# 0529_Agent_KitRev0103.net
KiCad netlist of a schematic drawn in EAGLE
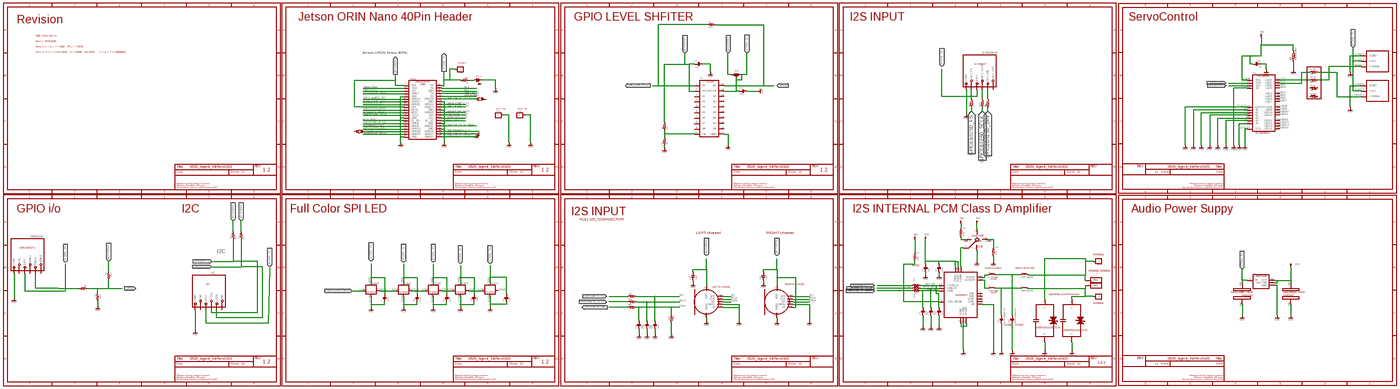
[diagram p0: schematic, sheet 1, overview]
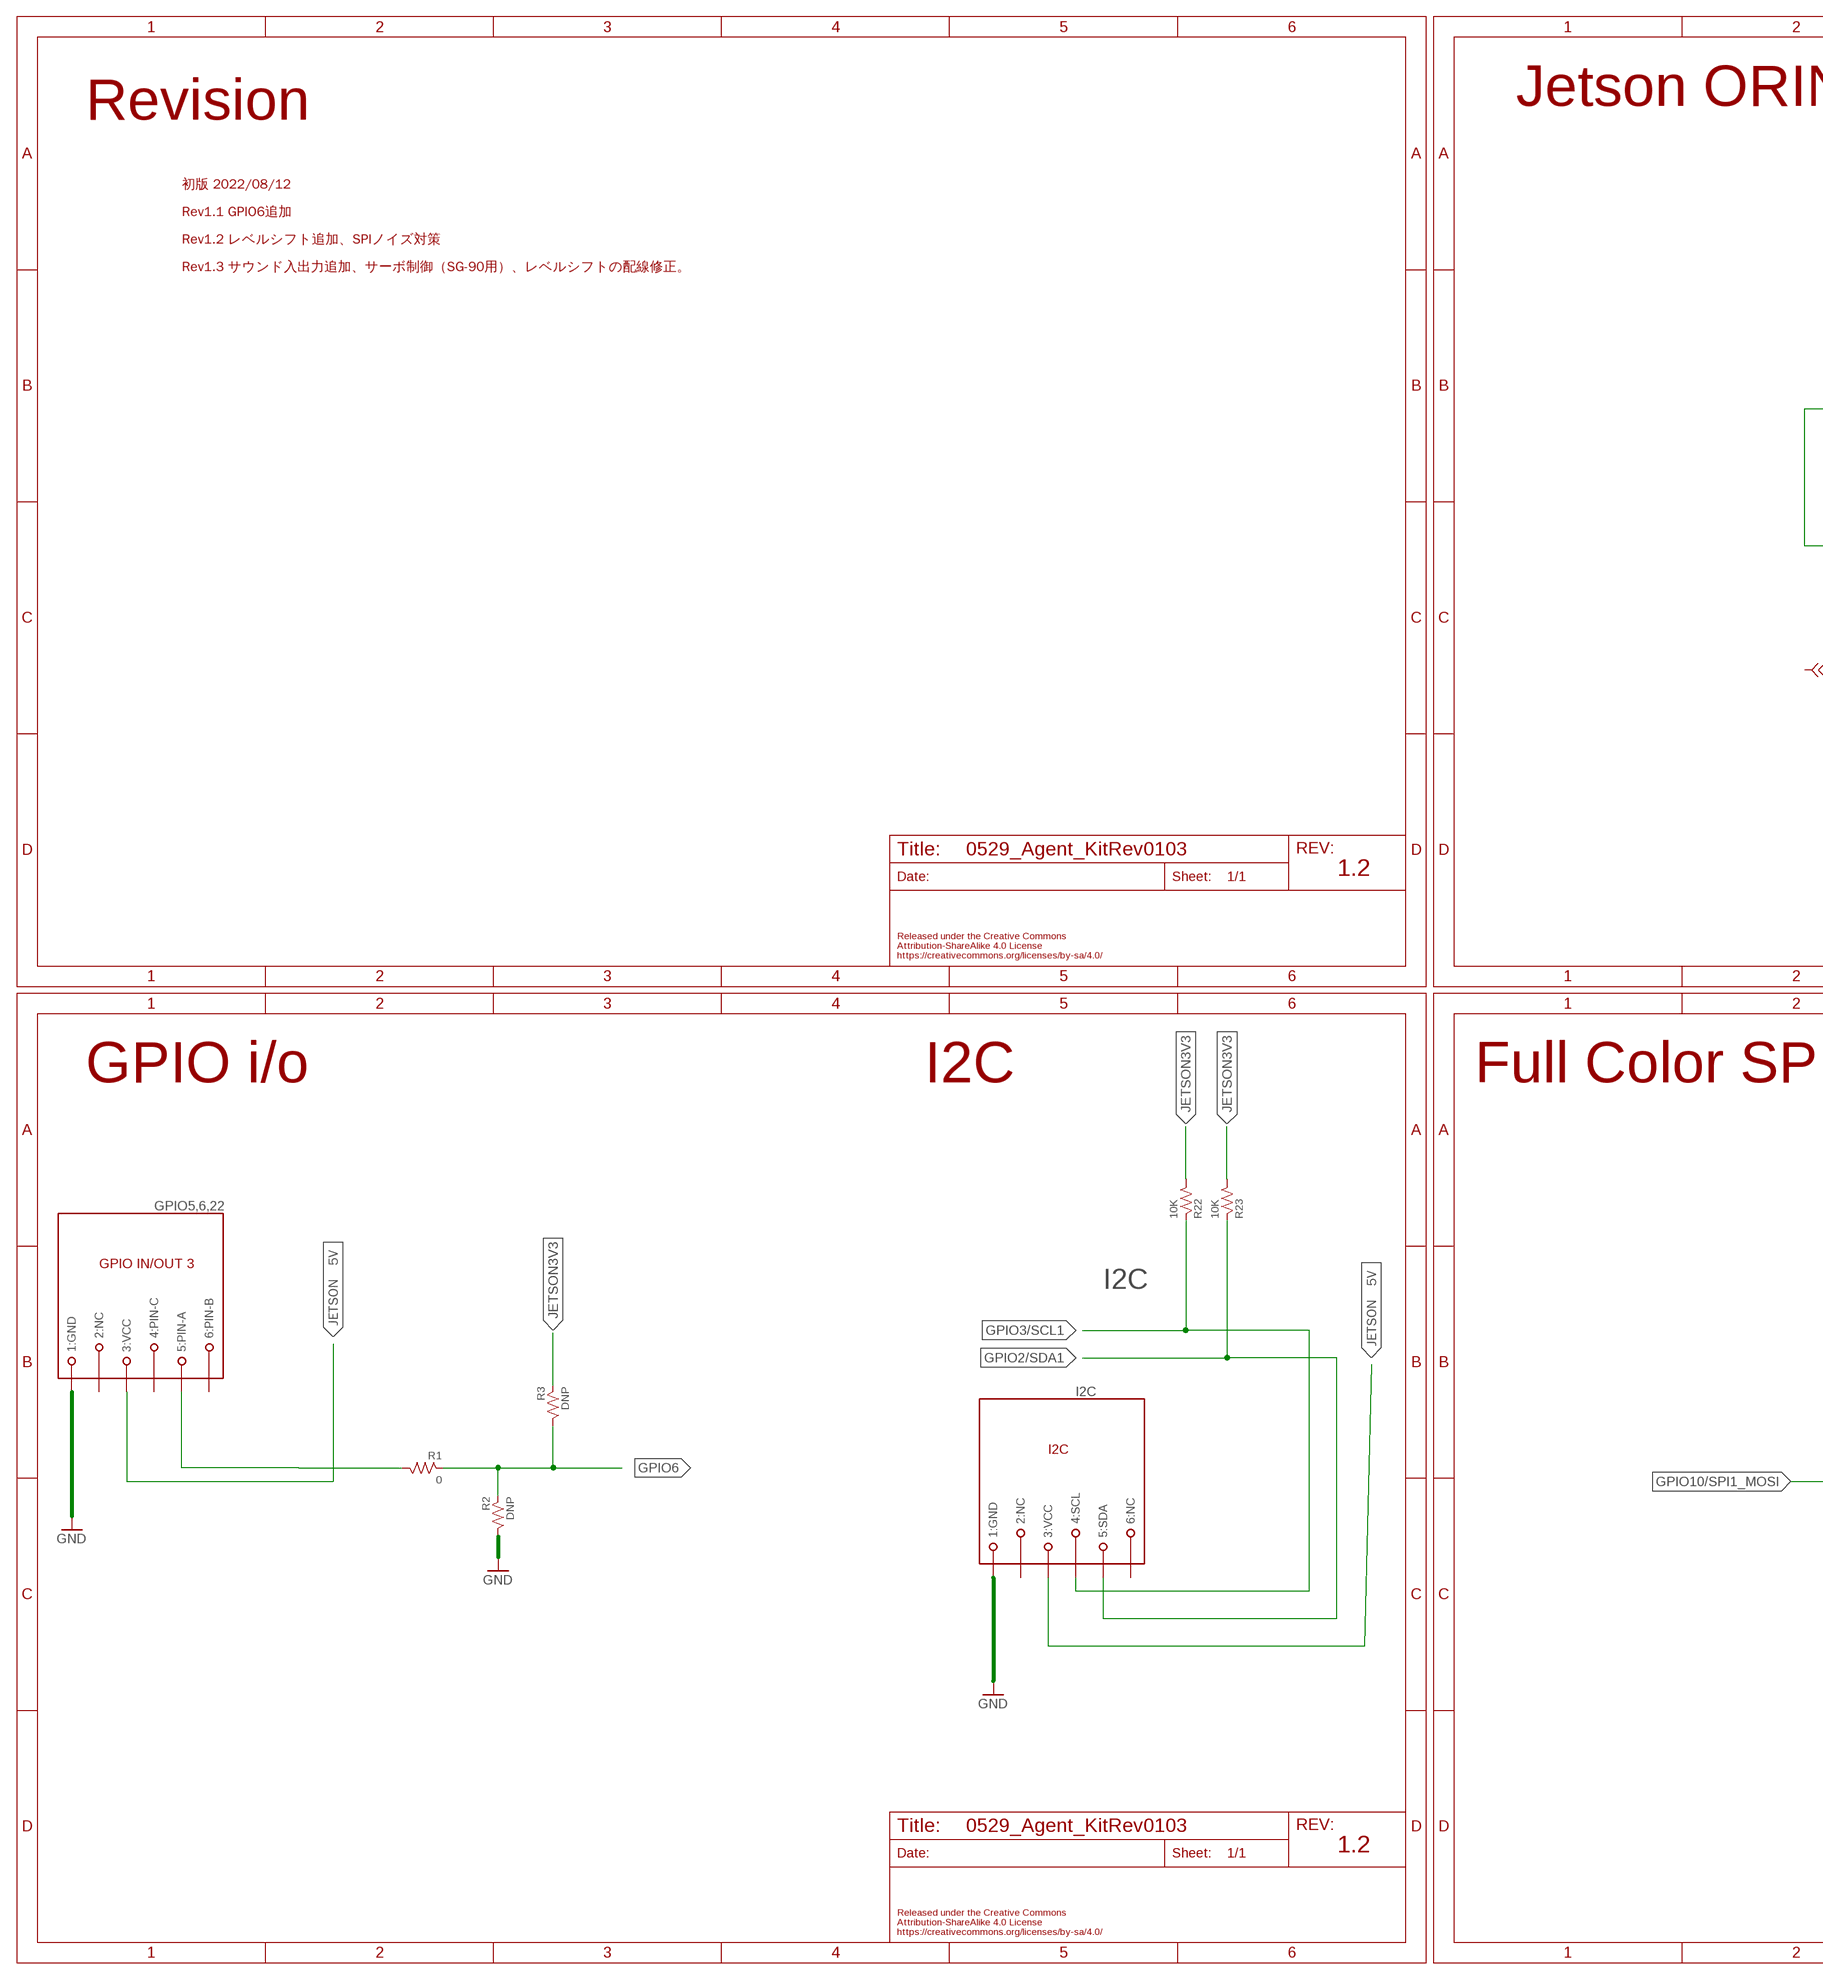
[diagram p1: schematic, sheet 1, part 1 of 4]
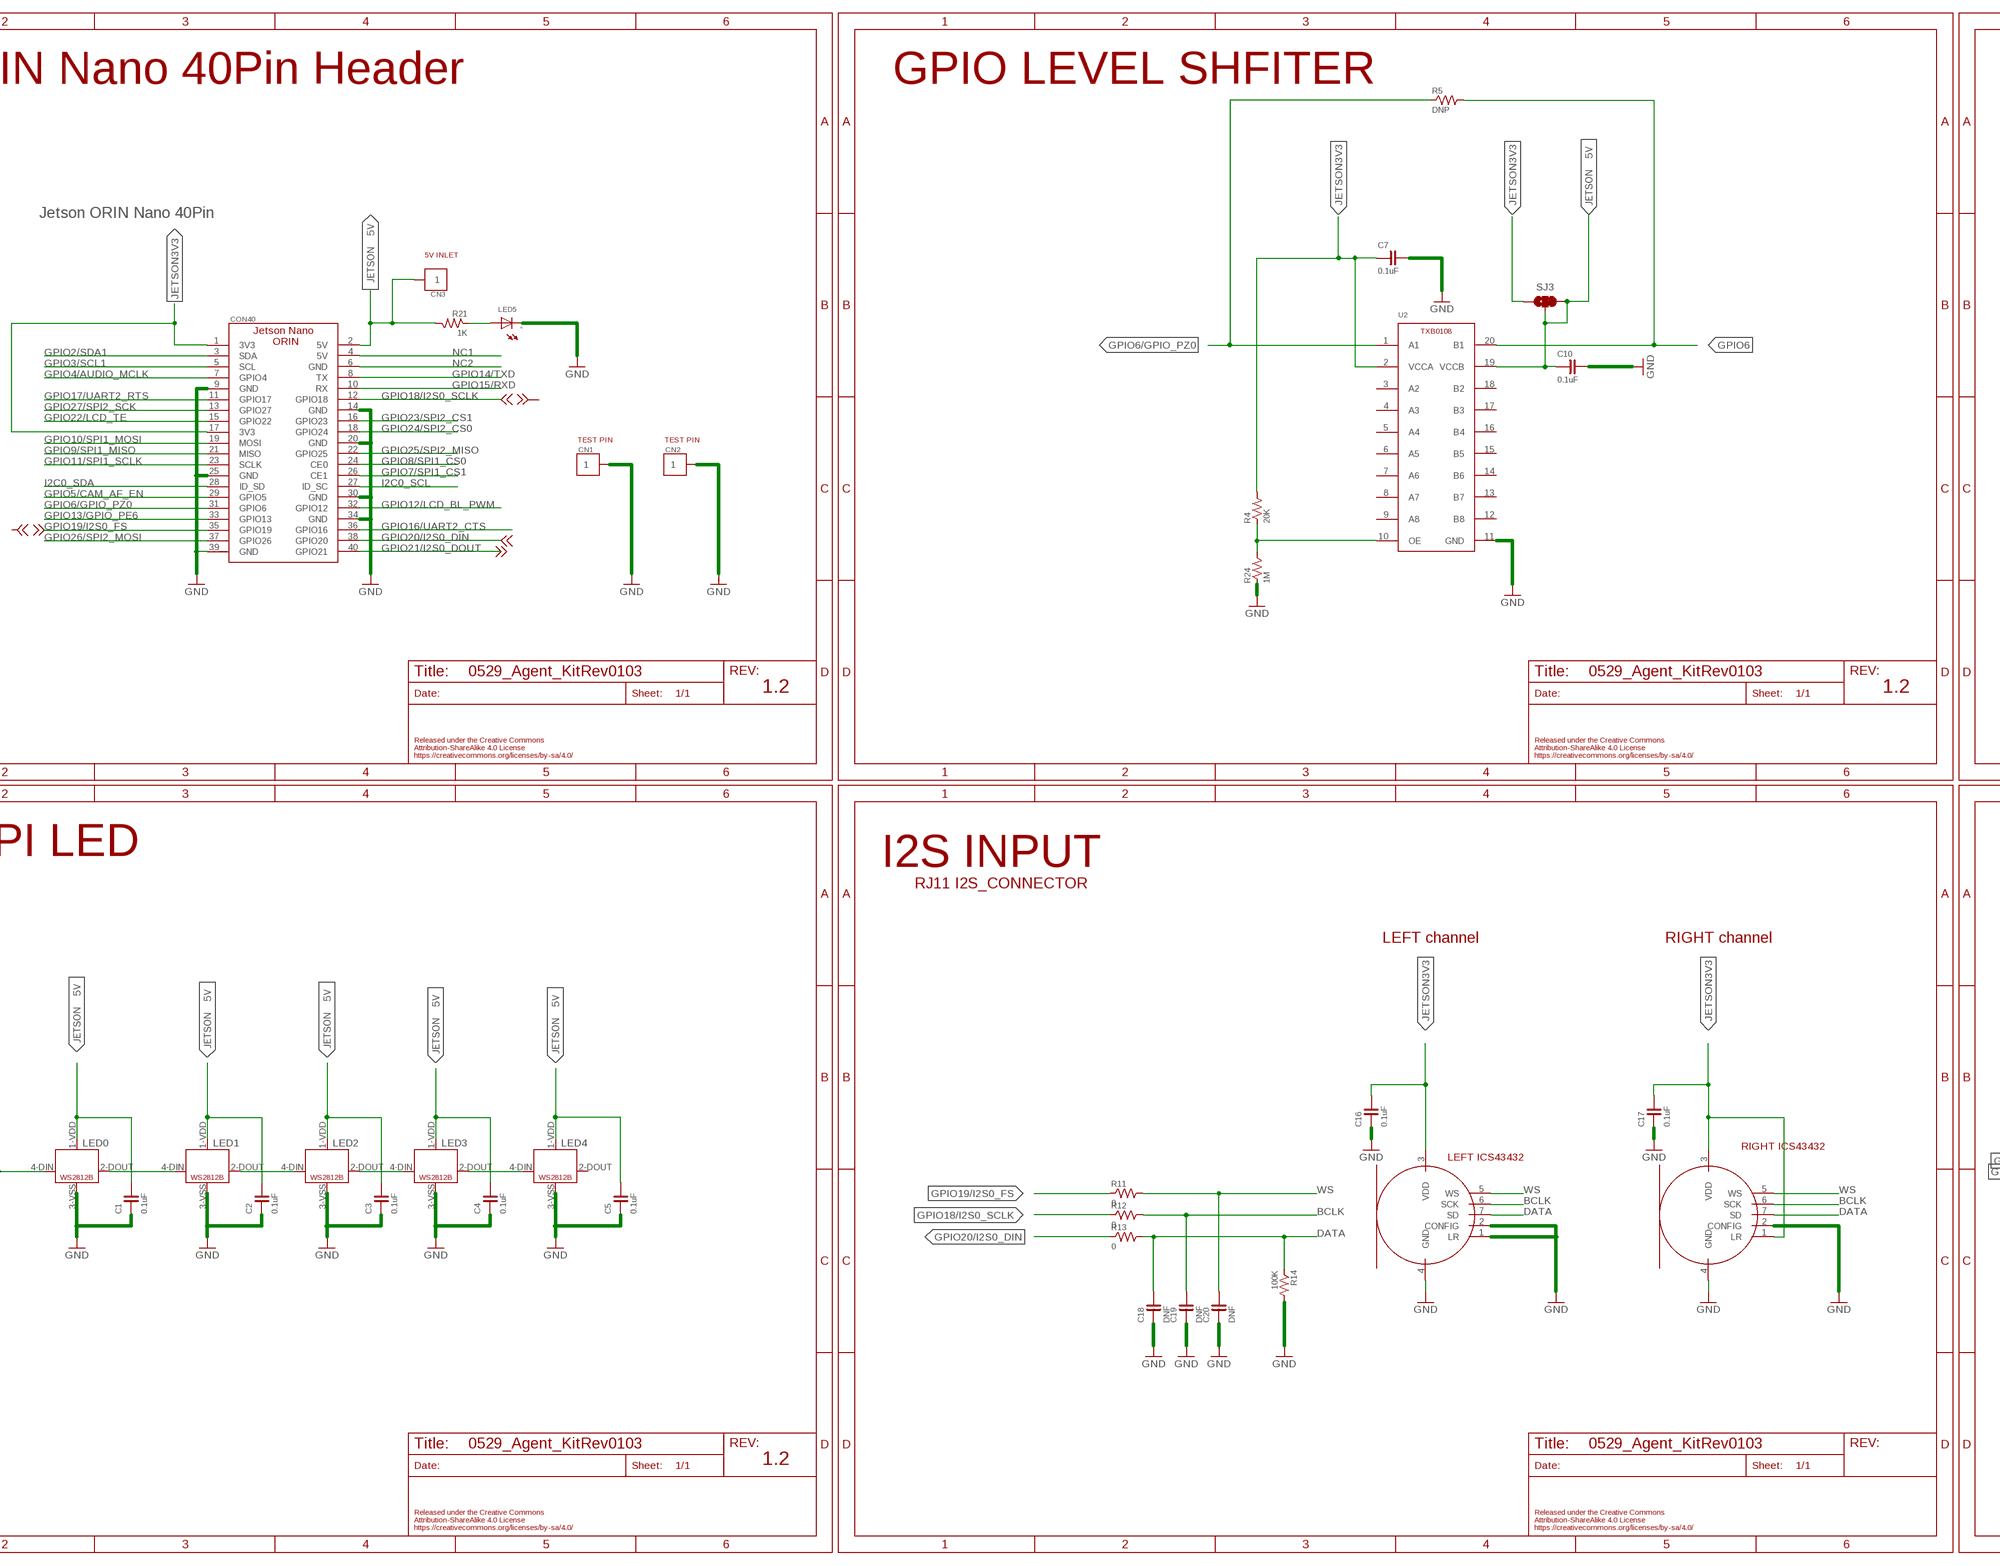
[diagram p2: schematic, sheet 1, part 2 of 4]
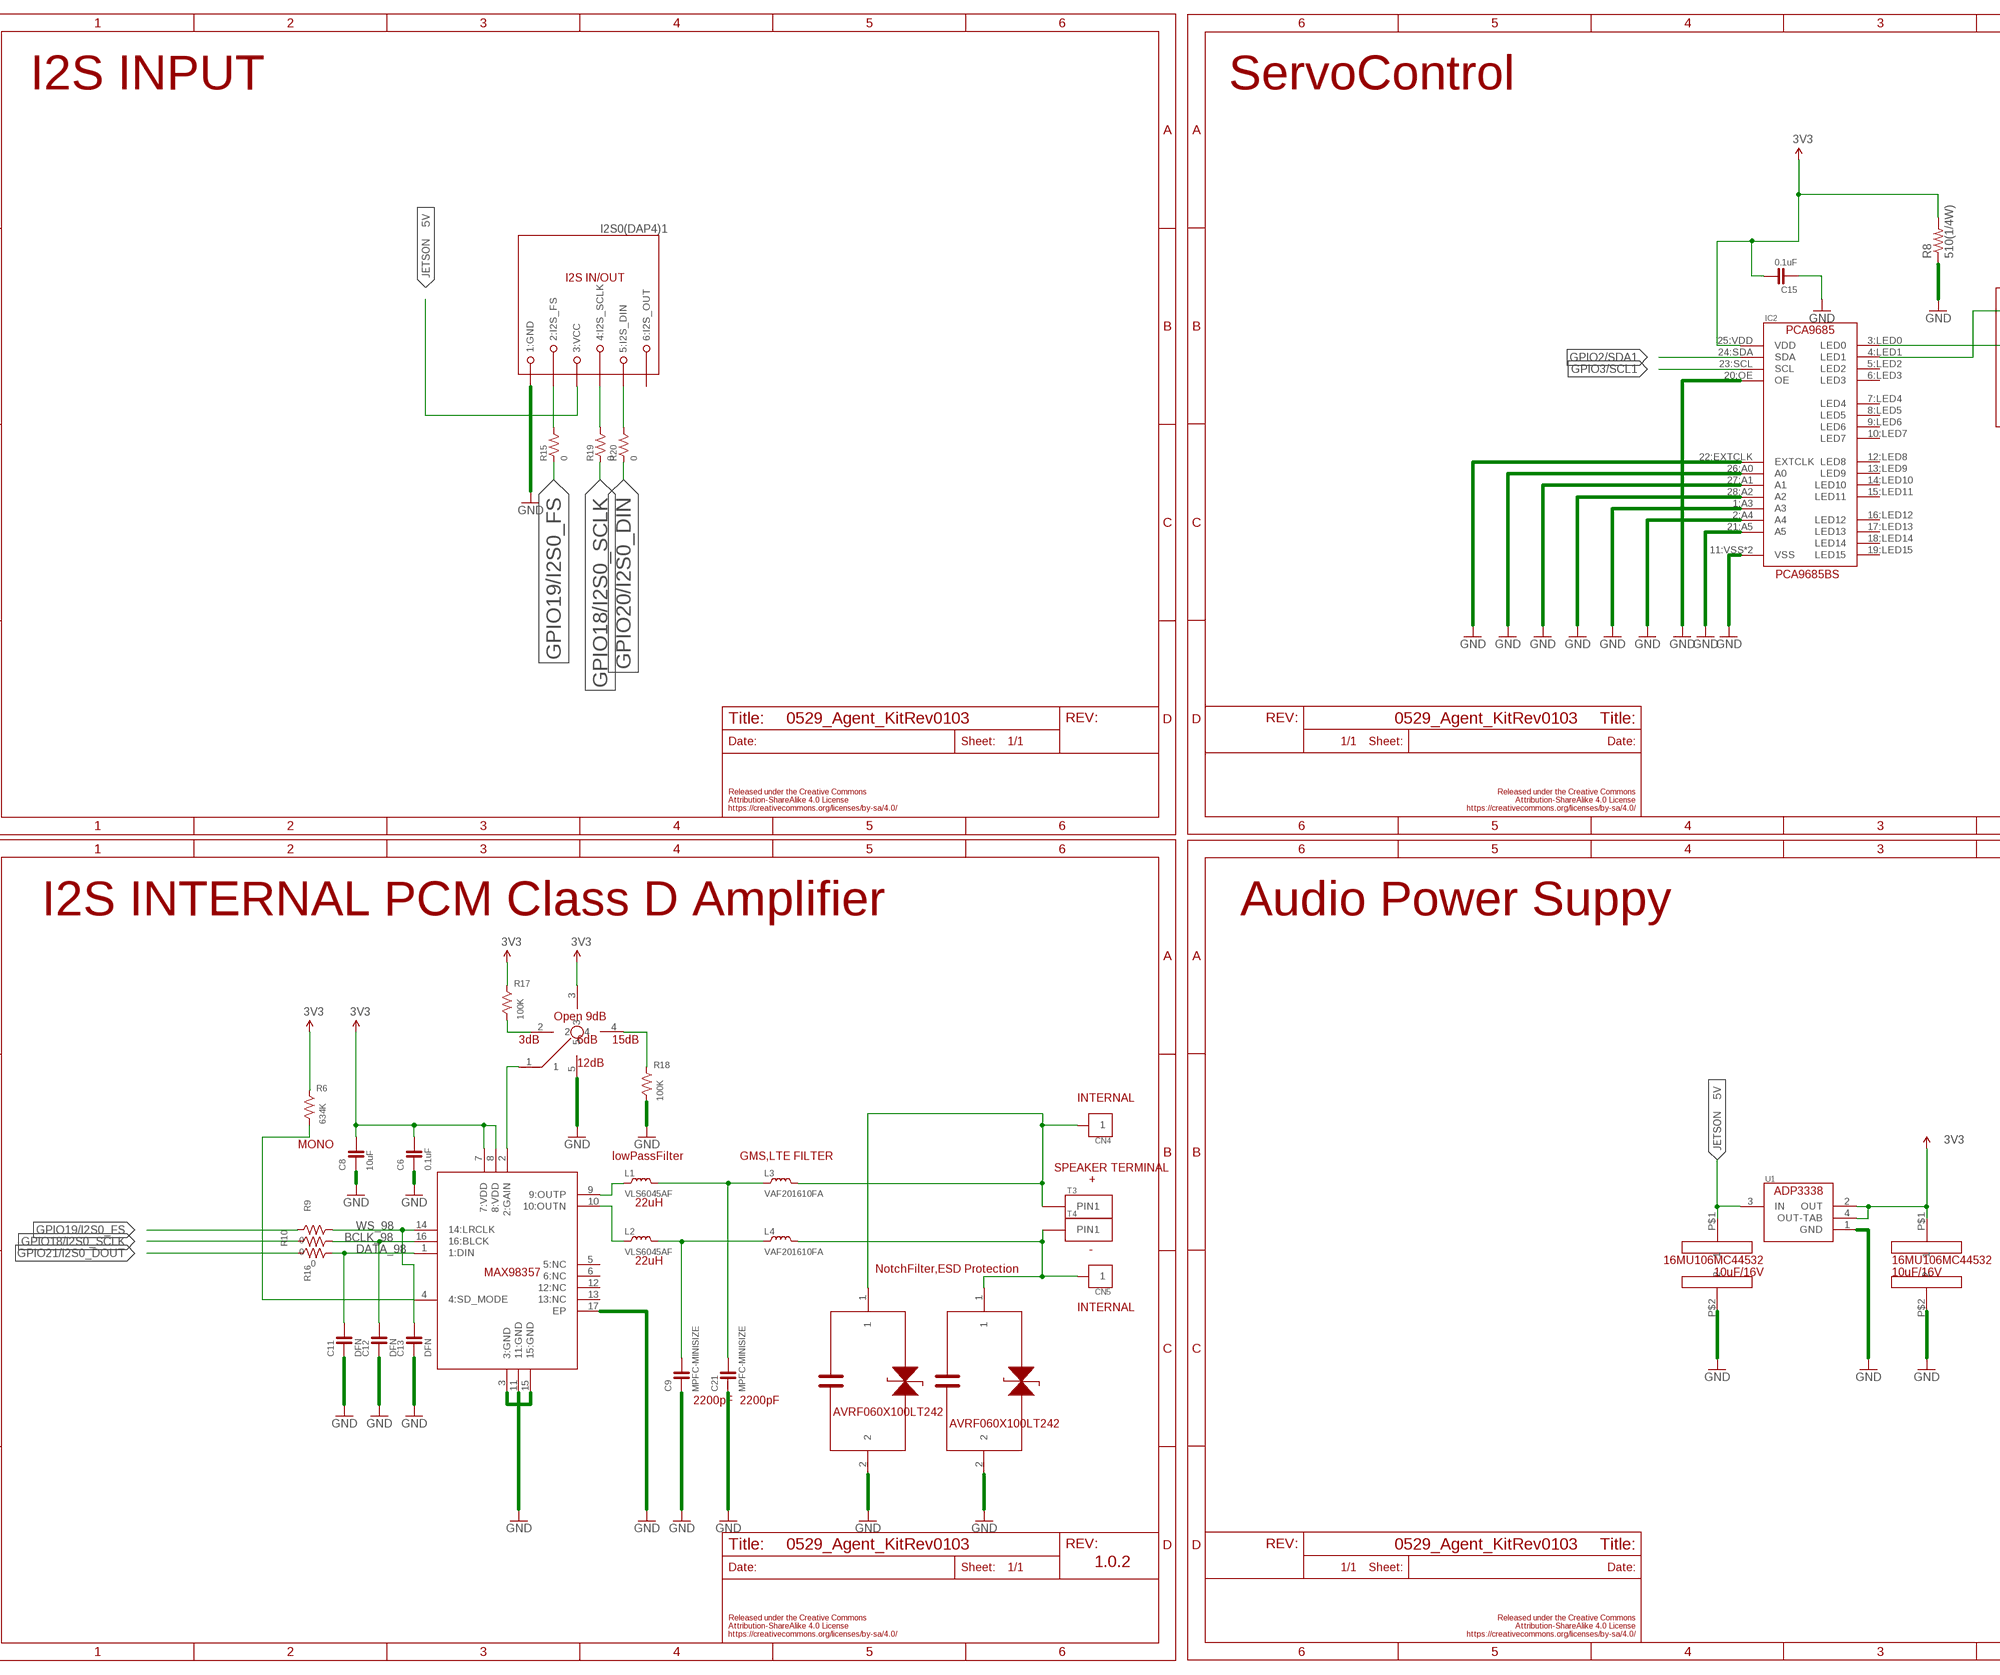
[diagram p3: schematic, sheet 1, part 3 of 4]
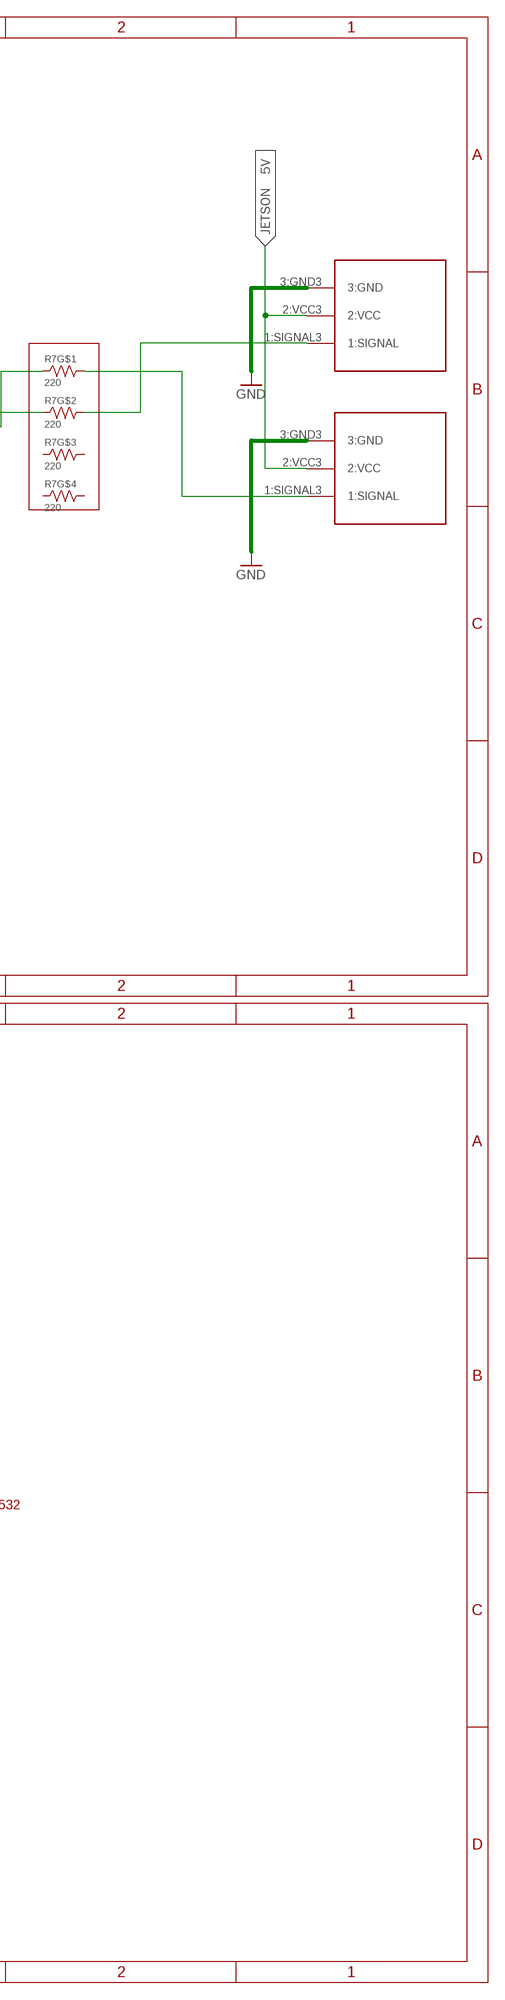
[diagram p4: schematic, sheet 1, part 4 of 4]

(export (version "E")
  (design (tool "Eeschema 10.0.6"))
  (components
    (comp (ref "C1")
      (value "0.1uF")
      (footprint "eagle-import:0603-NARROW")
      (libsource (lib "eagle-import") (part "CAPACITOR-0603_NARROW"))
    )
    (comp (ref "C2")
      (value "0.1uF")
      (footprint "eagle-import:0603-NARROW")
      (libsource (lib "eagle-import") (part "CAPACITOR-0603_NARROW"))
    )
    (comp (ref "C3")
      (value "0.1uF")
      (footprint "eagle-import:0603-NARROW")
      (libsource (lib "eagle-import") (part "CAPACITOR-0603_NARROW"))
    )
    (comp (ref "C4")
      (value "0.1uF")
      (footprint "eagle-import:0603-NARROW")
      (libsource (lib "eagle-import") (part "CAPACITOR-0603_NARROW"))
    )
    (comp (ref "C5")
      (value "0.1uF")
      (footprint "eagle-import:0603-NARROW")
      (libsource (lib "eagle-import") (part "CAPACITOR-0603_NARROW"))
    )
    (comp (ref "C6")
      (value "0.1uF")
      (footprint "eagle-import:0603")
      (libsource (lib "eagle-import") (part "CAPACITOR-0603"))
    )
    (comp (ref "C7")
      (value "0.1uF")
      (footprint "eagle-import:0603")
      (libsource (lib "eagle-import") (part "CAPACITOR-0603"))
    )
    (comp (ref "C8")
      (value "10uF")
      (footprint "eagle-import:0603")
      (libsource (lib "eagle-import") (part "CAPACITOR-0603"))
    )
    (comp (ref "C9")
      (value "MPFC-MINISIZE")
      (footprint "eagle-import:DIP-MPFC")
      (libsource (lib "eagle-import") (part "MPFC-MINISIZE"))
    )
    (comp (ref "C10")
      (value "0.1uF")
      (footprint "eagle-import:0603")
      (libsource (lib "eagle-import") (part "CAPACITOR-0603"))
    )
    (comp (ref "C11")
      (value "DFN")
      (footprint "eagle-import:0603")
      (libsource (lib "eagle-import") (part "CAPACITOR-0603"))
    )
    (comp (ref "C12")
      (value "DFN")
      (footprint "eagle-import:0603")
      (libsource (lib "eagle-import") (part "CAPACITOR-0603"))
    )
    (comp (ref "C13")
      (value "DFN")
      (footprint "eagle-import:0603")
      (libsource (lib "eagle-import") (part "CAPACITOR-0603"))
    )
    (comp (ref "C15")
      (value "0.1uF")
      (footprint "eagle-import:0603")
      (libsource (lib "eagle-import") (part "CAPACITOR-0603"))
    )
    (comp (ref "C16")
      (value "0.1uF")
      (footprint "eagle-import:0603")
      (libsource (lib "eagle-import") (part "CAPACITOR-0603"))
    )
    (comp (ref "C17")
      (value "0.1uF")
      (footprint "eagle-import:0603")
      (libsource (lib "eagle-import") (part "CAPACITOR-0603"))
    )
    (comp (ref "C18")
      (value "DNF")
      (footprint "eagle-import:0603")
      (libsource (lib "eagle-import") (part "CAPACITOR-0603"))
    )
    (comp (ref "C19")
      (value "DNF")
      (footprint "eagle-import:0603")
      (libsource (lib "eagle-import") (part "CAPACITOR-0603"))
    )
    (comp (ref "C20")
      (value "DNF")
      (footprint "eagle-import:0603")
      (libsource (lib "eagle-import") (part "CAPACITOR-0603"))
    )
    (comp (ref "C21")
      (value "MPFC-MINISIZE")
      (footprint "eagle-import:DIP-MPFC")
      (libsource (lib "eagle-import") (part "MPFC-MINISIZE"))
    )
    (comp (ref "C100")
      (value "POLIYMER_MULTI_LAYER_MU")
      (footprint "eagle-import:4532")
      (libsource (lib "eagle-import") (part "POLIYMER_MULTI_LAYER_MU"))
    )
    (comp (ref "C101")
      (value "POLIYMER_MULTI_LAYER_MU")
      (footprint "eagle-import:4532")
      (libsource (lib "eagle-import") (part "POLIYMER_MULTI_LAYER_MU"))
    )
    (comp (ref "CN1")
      (value "PIN_1X1-SMALL")
      (footprint "eagle-import:PIN_1X1_SMALL")
      (libsource (lib "eagle-import") (part "PIN_1X1-SMALL"))
    )
    (comp (ref "CN2")
      (value "PIN_1X1-SMALL")
      (footprint "eagle-import:PIN_1X1_SMALL")
      (libsource (lib "eagle-import") (part "PIN_1X1-SMALL"))
    )
    (comp (ref "CN3")
      (value "PIN_1X1-SMALL")
      (footprint "eagle-import:PIN_1X1_SMALL")
      (libsource (lib "eagle-import") (part "PIN_1X1-SMALL"))
    )
    (comp (ref "CN4")
      (value "PIN_1X1-SMALL")
      (footprint "eagle-import:PIN_1X1_SMALL")
      (libsource (lib "eagle-import") (part "PIN_1X1-SMALL"))
    )
    (comp (ref "CN5")
      (value "PIN_1X1-SMALL")
      (footprint "eagle-import:PIN_1X1_SMALL")
      (libsource (lib "eagle-import") (part "PIN_1X1-SMALL"))
    )
    (comp (ref "CON40")
      (value "JETSON_NANOJETSON_ORIN_NANO")
      (footprint "eagle-import:JETSON_ORIN_NANO_DIMENTION")
      (libsource (lib "eagle-import") (part "JETSON_NANOJETSON_ORIN_NANO"))
    )
    (comp (ref "GPIO5,6,22")
      (value "MODULAR-JACK-6P-RJ11_GPIO3")
      (footprint "eagle-import:7002-6PXC-X")
      (libsource (lib "eagle-import") (part "MODULAR-JACK-6P-RJ11_GPIO3"))
    )
    (comp (ref "I2C")
      (value "MODULAR-JACK-6P-RJ11_I2C")
      (footprint "eagle-import:7002-6PXC-X")
      (libsource (lib "eagle-import") (part "MODULAR-JACK-6P-RJ11_I2C"))
    )
    (comp (ref "I2S0(DAP4)1")
      (value "MODULAR-JACK-6P-RJ11_I2S_MASTER")
      (footprint "eagle-import:7002-6PXC-X")
      (libsource (lib "eagle-import") (part "MODULAR-JACK-6P-RJ11_I2S_MASTER"))
    )
    (comp (ref "IC2")
      (value "PCA9685BSPCA9685BS")
      (footprint "eagle-import:HVQFN28")
      (libsource (lib "eagle-import") (part "PCA9685BSPCA9685BS"))
    )
    (comp (ref "L1")
      (value "VLS6045AF")
      (footprint "eagle-import:VLS6045AF")
      (libsource (lib "eagle-import") (part "VLS6045AF"))
    )
    (comp (ref "L2")
      (value "VLS6045AF")
      (footprint "eagle-import:VLS6045AF")
      (libsource (lib "eagle-import") (part "VLS6045AF"))
    )
    (comp (ref "L3")
      (value "VAF201610FA")
      (footprint "eagle-import:VAF201610FA-1")
      (libsource (lib "eagle-import") (part "VAF201610FA"))
    )
    (comp (ref "L4")
      (value "VAF201610FA")
      (footprint "eagle-import:VAF201610FA-1")
      (libsource (lib "eagle-import") (part "VAF201610FA"))
    )
    (comp (ref "LED0")
      (value "WS2812B_NARROW")
      (footprint "eagle-import:WS2812B_NARROW")
      (libsource (lib "eagle-import") (part "WS2812B_NARROW"))
    )
    (comp (ref "LED1")
      (value "WS2812B_NARROW")
      (footprint "eagle-import:WS2812B_NARROW")
      (libsource (lib "eagle-import") (part "WS2812B_NARROW"))
    )
    (comp (ref "LED2")
      (value "WS2812B_NARROW")
      (footprint "eagle-import:WS2812B_NARROW")
      (libsource (lib "eagle-import") (part "WS2812B_NARROW"))
    )
    (comp (ref "LED3")
      (value "WS2812B_NARROW")
      (footprint "eagle-import:WS2812B_NARROW")
      (libsource (lib "eagle-import") (part "WS2812B_NARROW"))
    )
    (comp (ref "LED4")
      (value "WS2812B_NARROW")
      (footprint "eagle-import:WS2812B_NARROW")
      (libsource (lib "eagle-import") (part "WS2812B_NARROW"))
    )
    (comp (ref "LED5")
      (value "LED-0603")
      (footprint "eagle-import:0603")
      (libsource (lib "eagle-import") (part "LED-0603"))
    )
    (comp (ref "MIC_LEFT1")
      (value "TDK-ICS43432")
      (footprint "eagle-import:TDK-ICS43432")
      (libsource (lib "eagle-import") (part "TDK-ICS43432"))
    )
    (comp (ref "MIC_RIGHT1")
      (value "TDK-ICS43432")
      (footprint "eagle-import:TDK-ICS43432")
      (libsource (lib "eagle-import") (part "TDK-ICS43432"))
    )
    (comp (ref "R1")
      (value "0")
      (footprint "eagle-import:0603")
      (libsource (lib "eagle-import") (part "RESISTOR-0603"))
    )
    (comp (ref "R2")
      (value "DNP")
      (footprint "eagle-import:0603")
      (libsource (lib "eagle-import") (part "RESISTOR-0603"))
    )
    (comp (ref "R3")
      (value "DNP")
      (footprint "eagle-import:0603")
      (libsource (lib "eagle-import") (part "RESISTOR-0603"))
    )
    (comp (ref "R4")
      (value "20K")
      (footprint "eagle-import:0603")
      (libsource (lib "eagle-import") (part "RESISTOR-0603"))
    )
    (comp (ref "R5")
      (value "DNP")
      (footprint "eagle-import:0603")
      (libsource (lib "eagle-import") (part "RESISTOR-0603"))
    )
    (comp (ref "R6")
      (value "634K")
      (footprint "eagle-import:0603")
      (libsource (lib "eagle-import") (part "RESISTOR-0603"))
    )
    (comp (ref "R7")
      (value "220")
      (footprint "eagle-import:EXBV8V")
      (libsource (lib "eagle-import") (part "RESISTOR_ARRAY"))
    )
    (comp (ref "R8")
      (value "510(1/4W)")
      (footprint "eagle-import:R0805")
      (libsource (lib "eagle-import") (part "R-US_R0805"))
    )
    (comp (ref "R9")
      (value "0")
      (footprint "eagle-import:0603")
      (libsource (lib "eagle-import") (part "RESISTOR-0603"))
    )
    (comp (ref "R10")
      (value "0")
      (footprint "eagle-import:0603")
      (libsource (lib "eagle-import") (part "RESISTOR-0603"))
    )
    (comp (ref "R11")
      (value "0")
      (footprint "eagle-import:0603")
      (libsource (lib "eagle-import") (part "RESISTOR-0603"))
    )
    (comp (ref "R12")
      (value "0")
      (footprint "eagle-import:0603")
      (libsource (lib "eagle-import") (part "RESISTOR-0603"))
    )
    (comp (ref "R13")
      (value "0")
      (footprint "eagle-import:0603")
      (libsource (lib "eagle-import") (part "RESISTOR-0603"))
    )
    (comp (ref "R14")
      (value "100K")
      (footprint "eagle-import:0603")
      (libsource (lib "eagle-import") (part "RESISTOR-0603"))
    )
    (comp (ref "R15")
      (value "0")
      (footprint "eagle-import:0402")
      (libsource (lib "eagle-import") (part "RESISTOR-0402"))
    )
    (comp (ref "R16")
      (value "0")
      (footprint "eagle-import:0603")
      (libsource (lib "eagle-import") (part "RESISTOR-0603"))
    )
    (comp (ref "R17")
      (value "100K")
      (footprint "eagle-import:0603")
      (libsource (lib "eagle-import") (part "RESISTOR-0603"))
    )
    (comp (ref "R18")
      (value "100K")
      (footprint "eagle-import:0603")
      (libsource (lib "eagle-import") (part "RESISTOR-0603"))
    )
    (comp (ref "R19")
      (value "0")
      (footprint "eagle-import:0402")
      (libsource (lib "eagle-import") (part "RESISTOR-0402"))
    )
    (comp (ref "R20")
      (value "0")
      (footprint "eagle-import:0402")
      (libsource (lib "eagle-import") (part "RESISTOR-0402"))
    )
    (comp (ref "R21")
      (value "1K")
      (footprint "eagle-import:0603")
      (libsource (lib "eagle-import") (part "RESISTOR-0603"))
    )
    (comp (ref "R22")
      (value "10K")
      (footprint "eagle-import:0603")
      (libsource (lib "eagle-import") (part "RESISTOR-0603"))
    )
    (comp (ref "R23")
      (value "10K")
      (footprint "eagle-import:0603")
      (libsource (lib "eagle-import") (part "RESISTOR-0603"))
    )
    (comp (ref "R24")
      (value "1M")
      (footprint "eagle-import:0603")
      (libsource (lib "eagle-import") (part "RESISTOR-0603"))
    )
    (comp (ref "SJ3")
      (value "SMD-JUMPER-3-23SHORT")
      (footprint "eagle-import:SMD-JUMPER-3")
      (libsource (lib "eagle-import") (part "SMD-JUMPER-3-23SHORT"))
    )
    (comp (ref "T3")
      (value "TBL004-508")
      (footprint "eagle-import:TBL004-508")
      (libsource (lib "eagle-import") (part "TBL004-508"))
    )
    (comp (ref "T4")
      (value "TBL004-508")
      (footprint "eagle-import:TBL004-508")
      (libsource (lib "eagle-import") (part "TBL004-508"))
    )
    (comp (ref "U$10")
      (value "RC_3PIN_SERVO")
      (footprint "eagle-import:PNHEADER_2.54_SMT_3PIN_RC_TT01_02")
      (libsource (lib "eagle-import") (part "RC_3PIN_SERVO"))
    )
    (comp (ref "U$11")
      (value "AVRF060X100LT242")
      (footprint "eagle-import:AVRF0X0X100LT_0603")
      (libsource (lib "eagle-import") (part "AVRF060X100LT242"))
    )
    (comp (ref "U$12")
      (value "AVRF060X100LT242")
      (footprint "eagle-import:AVRF0X0X100LT_0603")
      (libsource (lib "eagle-import") (part "AVRF060X100LT242"))
    )
    (comp (ref "U$13")
      (value "MAX98357A,B")
      (footprint "eagle-import:TQFN(16L3_3_0.75)")
      (libsource (lib "eagle-import") (part "MAX98357A,B"))
    )
    (comp (ref "U$14")
      (value "2MMJUMPER_CROSS")
      (footprint "eagle-import:PINHEAD2MM_CROSS")
      (libsource (lib "eagle-import") (part "2MMJUMPER_CROSS"))
    )
    (comp (ref "U$16")
      (value "RC_3PIN_SERVO")
      (footprint "eagle-import:PNHEADER_2.54_SMT_3PIN_RC_TT01_02")
      (libsource (lib "eagle-import") (part "RC_3PIN_SERVO"))
    )
    (comp (ref "U1")
      (value "ADP3338AKCZ")
      (footprint "eagle-import:SOT-223-KC3")
      (libsource (lib "eagle-import") (part "ADP3338AKCZ"))
    )
    (comp (ref "U2")
      (value "TXB0108")
      (footprint "eagle-import:R-PUSON-N20")
      (libsource (lib "eagle-import") (part "TXB0108"))
    )
  )
  (nets
    (net (code "1") (name "/BCLK") (class "Default")
      (node (ref "C19") (pin "2") (pinfunction "2_2") (pintype "passive"))
      (node (ref "MIC_LEFT1") (pin "6") (pinfunction "SCK_6") (pintype "bidirectional"))
      (node (ref "MIC_RIGHT1") (pin "6") (pinfunction "SCK_6") (pintype "bidirectional"))
      (node (ref "R12") (pin "2") (pinfunction "2_2") (pintype "bidirectional"))
    )
    (net (code "2") (name "/BCLK_98") (class "Default")
      (node (ref "C12") (pin "2") (pinfunction "2_2") (pintype "passive"))
      (node (ref "R10") (pin "2") (pinfunction "2_2") (pintype "bidirectional"))
      (node (ref "U$13") (pin "16") (pinfunction "16:BLCK_16") (pintype "bidirectional"))
    )
    (net (code "3") (name "/DATA") (class "Default")
      (node (ref "C18") (pin "2") (pinfunction "2_2") (pintype "passive"))
      (node (ref "MIC_LEFT1") (pin "7") (pinfunction "SD_7") (pintype "bidirectional"))
      (node (ref "MIC_RIGHT1") (pin "7") (pinfunction "SD_7") (pintype "bidirectional"))
      (node (ref "R13") (pin "2") (pinfunction "2_2") (pintype "bidirectional"))
      (node (ref "R14") (pin "1") (pinfunction "1_1") (pintype "bidirectional"))
    )
    (net (code "4") (name "/DATA_98") (class "Default")
      (node (ref "C11") (pin "2") (pinfunction "2_2") (pintype "passive"))
      (node (ref "R16") (pin "2") (pinfunction "2_2") (pintype "bidirectional"))
      (node (ref "U$13") (pin "1") (pinfunction "1:DIN_1") (pintype "bidirectional"))
    )
    (net (code "5") (name "/GPIO4{slash}AUDIO_MCLK") (class "Default")
      (node (ref "CON40") (pin "7") (pinfunction "GPIO4_7") (pintype "bidirectional"))
    )
    (net (code "6") (name "/GPIO5{slash}CAM_AF_EN") (class "Default")
      (node (ref "CON40") (pin "29") (pinfunction "GPIO5_29") (pintype "bidirectional"))
    )
    (net (code "7") (name "/GPIO7{slash}SPI1_CS1") (class "Default")
      (node (ref "CON40") (pin "26") (pinfunction "CE1_26") (pintype "bidirectional"))
    )
    (net (code "8") (name "/GPIO8{slash}SPI1_CS0") (class "Default")
      (node (ref "CON40") (pin "24") (pinfunction "CE0_24") (pintype "bidirectional"))
    )
    (net (code "9") (name "/GPIO9{slash}SPI1_MISO") (class "Default")
      (node (ref "CON40") (pin "21") (pinfunction "MISO_21") (pintype "bidirectional"))
    )
    (net (code "10") (name "/GPIO11{slash}SPI1_SCLK") (class "Default")
      (node (ref "CON40") (pin "23") (pinfunction "SCLK_23") (pintype "bidirectional"))
    )
    (net (code "11") (name "/GPIO12{slash}LCD_BL_PWM") (class "Default")
      (node (ref "CON40") (pin "32") (pinfunction "GPIO12_32") (pintype "bidirectional"))
    )
    (net (code "12") (name "/GPIO13{slash}GPIO_PE6") (class "Default")
      (node (ref "CON40") (pin "33") (pinfunction "GPIO13_33") (pintype "bidirectional"))
    )
    (net (code "13") (name "/GPIO14{slash}TXD") (class "Default")
      (node (ref "CON40") (pin "8") (pinfunction "TX_8") (pintype "bidirectional"))
    )
    (net (code "14") (name "/GPIO15{slash}RXD") (class "Default")
      (node (ref "CON40") (pin "10") (pinfunction "RX_10") (pintype "bidirectional"))
    )
    (net (code "15") (name "/GPIO16{slash}UART2_CTS") (class "Default")
      (node (ref "CON40") (pin "36") (pinfunction "GPIO16_36") (pintype "bidirectional"))
    )
    (net (code "16") (name "/GPIO17{slash}UART2_RTS") (class "Default")
      (node (ref "CON40") (pin "11") (pinfunction "GPIO17_11") (pintype "bidirectional"))
    )
    (net (code "17") (name "/GPIO22{slash}LCD_TE") (class "Default")
      (node (ref "CON40") (pin "15") (pinfunction "GPIO22_15") (pintype "bidirectional"))
    )
    (net (code "18") (name "/GPIO23{slash}SPI2_CS1") (class "Default")
      (node (ref "CON40") (pin "16") (pinfunction "GPIO23_16") (pintype "bidirectional"))
    )
    (net (code "19") (name "/GPIO24{slash}SPI2_CS0") (class "Default")
      (node (ref "CON40") (pin "18") (pinfunction "GPIO24_18") (pintype "bidirectional"))
    )
    (net (code "20") (name "/GPIO25{slash}SPI2_MISO") (class "Default")
      (node (ref "CON40") (pin "22") (pinfunction "GPIO25_22") (pintype "bidirectional"))
    )
    (net (code "21") (name "/GPIO26{slash}SPI2_MOSI") (class "Default")
      (node (ref "CON40") (pin "37") (pinfunction "GPIO26_37") (pintype "bidirectional"))
    )
    (net (code "22") (name "/GPIO27{slash}SPI2_SCK") (class "Default")
      (node (ref "CON40") (pin "13") (pinfunction "GPIO27_13") (pintype "bidirectional"))
    )
    (net (code "23") (name "/I2C0_SCL") (class "Default")
      (node (ref "CON40") (pin "27") (pinfunction "ID_SC_27") (pintype "bidirectional"))
    )
    (net (code "24") (name "/I2C0_SDA") (class "Default")
      (node (ref "CON40") (pin "28") (pinfunction "ID_SD_28") (pintype "bidirectional"))
    )
    (net (code "25") (name "/NC1") (class "Default")
      (node (ref "CON40") (pin "4") (pinfunction "5V_4") (pintype "bidirectional"))
    )
    (net (code "26") (name "/NC2") (class "Default")
      (node (ref "CON40") (pin "6") (pinfunction "GND_6") (pintype "bidirectional"))
    )
    (net (code "27") (name "/WS") (class "Default")
      (node (ref "C20") (pin "2") (pinfunction "2_2") (pintype "passive"))
      (node (ref "MIC_LEFT1") (pin "5") (pinfunction "WS_5") (pintype "bidirectional"))
      (node (ref "MIC_RIGHT1") (pin "5") (pinfunction "WS_5") (pintype "bidirectional"))
      (node (ref "R11") (pin "2") (pinfunction "2_2") (pintype "bidirectional"))
    )
    (net (code "28") (name "/WS_98") (class "Default")
      (node (ref "C13") (pin "2") (pinfunction "2_2") (pintype "passive"))
      (node (ref "R9") (pin "2") (pinfunction "2_2") (pintype "bidirectional"))
      (node (ref "U$13") (pin "14") (pinfunction "14:LRCLK_14") (pintype "bidirectional"))
    )
    (net (code "29") (name "3V3") (class "Default")
      (node (ref "C101") (pin "P$1") (pinfunction "1_P$1") (pintype "bidirectional"))
      (node (ref "C15") (pin "2") (pinfunction "2_2") (pintype "passive"))
      (node (ref "C6") (pin "2") (pinfunction "2_2") (pintype "passive"))
      (node (ref "C8") (pin "2") (pinfunction "2_2") (pintype "passive"))
      (node (ref "IC2") (pin "25:VDD") (pinfunction "VDD_25:VDD") (pintype "bidirectional"))
      (node (ref "R17") (pin "1") (pinfunction "1_1") (pintype "bidirectional"))
      (node (ref "R6") (pin "1") (pinfunction "1_1") (pintype "bidirectional"))
      (node (ref "R8") (pin "2") (pinfunction "2_2") (pintype "passive"))
      (node (ref "U$13") (pin "7") (pinfunction "7:VDD_7") (pintype "bidirectional"))
      (node (ref "U$13") (pin "8") (pinfunction "8:VDD_8") (pintype "bidirectional"))
      (node (ref "U$14") (pin "3") (pinfunction "3_3") (pintype "bidirectional"))
      (node (ref "U1") (pin "2") (pinfunction "OUT_2") (pintype "bidirectional"))
      (node (ref "U1") (pin "4") (pinfunction "OUT-TAB_4") (pintype "bidirectional"))
    )
    (net (code "30") (name "GND") (class "Default")
      (node (ref "C1") (pin "1") (pinfunction "1_1") (pintype "passive"))
      (node (ref "C10") (pin "2") (pinfunction "2_2") (pintype "passive"))
      (node (ref "C100") (pin "P$2") (pinfunction "2_P$2") (pintype "bidirectional"))
      (node (ref "C101") (pin "P$2") (pinfunction "2_P$2") (pintype "bidirectional"))
      (node (ref "C11") (pin "1") (pinfunction "1_1") (pintype "passive"))
      (node (ref "C12") (pin "1") (pinfunction "1_1") (pintype "passive"))
      (node (ref "C13") (pin "1") (pinfunction "1_1") (pintype "passive"))
      (node (ref "C15") (pin "1") (pinfunction "1_1") (pintype "passive"))
      (node (ref "C16") (pin "1") (pinfunction "1_1") (pintype "passive"))
      (node (ref "C17") (pin "1") (pinfunction "1_1") (pintype "passive"))
      (node (ref "C18") (pin "1") (pinfunction "1_1") (pintype "passive"))
      (node (ref "C19") (pin "1") (pinfunction "1_1") (pintype "passive"))
      (node (ref "C2") (pin "1") (pinfunction "1_1") (pintype "passive"))
      (node (ref "C20") (pin "1") (pinfunction "1_1") (pintype "passive"))
      (node (ref "C21") (pin "1") (pinfunction "1_1") (pintype "passive"))
      (node (ref "C3") (pin "1") (pinfunction "1_1") (pintype "passive"))
      (node (ref "C4") (pin "1") (pinfunction "1_1") (pintype "passive"))
      (node (ref "C5") (pin "1") (pinfunction "1_1") (pintype "passive"))
      (node (ref "C6") (pin "1") (pinfunction "1_1") (pintype "passive"))
      (node (ref "C7") (pin "2") (pinfunction "2_2") (pintype "passive"))
      (node (ref "C8") (pin "1") (pinfunction "1_1") (pintype "passive"))
      (node (ref "C9") (pin "1") (pinfunction "1_1") (pintype "passive"))
      (node (ref "CN1") (pin "1") (pinfunction "1_1") (pintype "bidirectional"))
      (node (ref "CN2") (pin "1") (pinfunction "1_1") (pintype "bidirectional"))
      (node (ref "CON40") (pin "14") (pinfunction "GND_14") (pintype "bidirectional"))
      (node (ref "CON40") (pin "20") (pinfunction "GND_20") (pintype "bidirectional"))
      (node (ref "CON40") (pin "25") (pinfunction "GND_25") (pintype "bidirectional"))
      (node (ref "CON40") (pin "30") (pinfunction "GND_30") (pintype "bidirectional"))
      (node (ref "CON40") (pin "34") (pinfunction "GND_34") (pintype "bidirectional"))
      (node (ref "CON40") (pin "39") (pinfunction "GND_39") (pintype "bidirectional"))
      (node (ref "CON40") (pin "9") (pinfunction "GND_9") (pintype "bidirectional"))
      (node (ref "GPIO5,6,22") (pin "1") (pinfunction "1:GND_1") (pintype "power_in"))
      (node (ref "I2C") (pin "1") (pinfunction "1:GND_1") (pintype "power_in"))
      (node (ref "I2S0(DAP4)1") (pin "1") (pinfunction "1:GND_1") (pintype "power_in"))
      (node (ref "IC2") (pin "11:VSS") (pinfunction "VSS_11:VSS") (pintype "bidirectional"))
      (node (ref "IC2") (pin "1:A3") (pinfunction "A3_1:A3") (pintype "bidirectional"))
      (node (ref "IC2") (pin "20:OE") (pinfunction "OE_20:OE") (pintype "bidirectional"))
      (node (ref "IC2") (pin "21:A5") (pinfunction "A5_21:A5") (pintype "bidirectional"))
      (node (ref "IC2") (pin "22:EXTCLK") (pinfunction "EXTCLK_22:EXTCLK") (pintype "bidirectional"))
      (node (ref "IC2") (pin "26:A0") (pinfunction "A0_26:A0") (pintype "bidirectional"))
      (node (ref "IC2") (pin "27:A1") (pinfunction "A1_27:A1") (pintype "bidirectional"))
      (node (ref "IC2") (pin "28:A2") (pinfunction "A2_28:A2") (pintype "bidirectional"))
      (node (ref "IC2") (pin "29") (pinfunction "VSS_29") (pintype "bidirectional"))
      (node (ref "IC2") (pin "2:A4") (pinfunction "A4_2:A4") (pintype "bidirectional"))
      (node (ref "LED0") (pin "3-VSS") (pinfunction "VSS_3-VSS") (pintype "bidirectional"))
      (node (ref "LED1") (pin "3-VSS") (pinfunction "VSS_3-VSS") (pintype "bidirectional"))
      (node (ref "LED2") (pin "3-VSS") (pinfunction "VSS_3-VSS") (pintype "bidirectional"))
      (node (ref "LED3") (pin "3-VSS") (pinfunction "VSS_3-VSS") (pintype "bidirectional"))
      (node (ref "LED4") (pin "3-VSS") (pinfunction "VSS_3-VSS") (pintype "bidirectional"))
      (node (ref "LED5") (pin "CATHODE") (pinfunction "CATHODE_CATHODE") (pintype "passive"))
      (node (ref "MIC_LEFT1") (pin "1") (pinfunction "LR_1") (pintype "bidirectional"))
      (node (ref "MIC_LEFT1") (pin "2") (pinfunction "CONFIG_2") (pintype "bidirectional"))
      (node (ref "MIC_LEFT1") (pin "4") (pinfunction "GND_4") (pintype "bidirectional"))
      (node (ref "MIC_RIGHT1") (pin "2") (pinfunction "CONFIG_2") (pintype "bidirectional"))
      (node (ref "MIC_RIGHT1") (pin "4") (pinfunction "GND_4") (pintype "bidirectional"))
      (node (ref "R14") (pin "2") (pinfunction "2_2") (pintype "bidirectional"))
      (node (ref "R18") (pin "2") (pinfunction "2_2") (pintype "bidirectional"))
      (node (ref "R2") (pin "2") (pinfunction "2_2") (pintype "bidirectional"))
      (node (ref "R24") (pin "1") (pinfunction "1_1") (pintype "bidirectional"))
      (node (ref "R8") (pin "1") (pinfunction "1_1") (pintype "passive"))
      (node (ref "U$10") (pin "3:GND3") (pinfunction "3:GND_3:GND3") (pintype "bidirectional"))
      (node (ref "U$11") (pin "2") (pinfunction "2_2") (pintype "bidirectional"))
      (node (ref "U$12") (pin "2") (pinfunction "2_2") (pintype "bidirectional"))
      (node (ref "U$13") (pin "11") (pinfunction "11:GND_11") (pintype "bidirectional"))
      (node (ref "U$13") (pin "15") (pinfunction "15:GND_15") (pintype "bidirectional"))
      (node (ref "U$13") (pin "17") (pinfunction "EP_17") (pintype "bidirectional"))
      (node (ref "U$13") (pin "3") (pinfunction "3:GND_3") (pintype "bidirectional"))
      (node (ref "U$14") (pin "5") (pinfunction "5_5") (pintype "bidirectional"))
      (node (ref "U$16") (pin "3:GND3") (pinfunction "3:GND_3:GND3") (pintype "bidirectional"))
      (node (ref "U1") (pin "1") (pinfunction "GND_1") (pintype "bidirectional"))
      (node (ref "U2") (pin "11") (pinfunction "GND_11") (pintype "bidirectional"))
    )
    (net (code "31") (name "GPIO2{slash}SDA1") (class "Default")
      (node (ref "CON40") (pin "3") (pinfunction "SDA_3") (pintype "bidirectional"))
      (node (ref "I2C") (pin "5") (pinfunction "5:SDA_5") (pintype "open_collector"))
      (node (ref "IC2") (pin "24:SDA") (pinfunction "SDA_24:SDA") (pintype "bidirectional"))
      (node (ref "R23") (pin "1") (pinfunction "1_1") (pintype "bidirectional"))
    )
    (net (code "32") (name "GPIO3{slash}SCL1") (class "Default")
      (node (ref "CON40") (pin "5") (pinfunction "SCL_5") (pintype "bidirectional"))
      (node (ref "I2C") (pin "4") (pinfunction "4:SCL_4") (pintype "open_collector"))
      (node (ref "IC2") (pin "23:SCL") (pinfunction "SCL_23:SCL") (pintype "bidirectional"))
      (node (ref "R22") (pin "1") (pinfunction "1_1") (pintype "bidirectional"))
    )
    (net (code "33") (name "GPIO6") (class "Default")
      (node (ref "R1") (pin "1") (pinfunction "1_1") (pintype "bidirectional"))
      (node (ref "R2") (pin "1") (pinfunction "1_1") (pintype "bidirectional"))
      (node (ref "R3") (pin "2") (pinfunction "2_2") (pintype "bidirectional"))
      (node (ref "R5") (pin "2") (pinfunction "2_2") (pintype "bidirectional"))
      (node (ref "U2") (pin "20") (pinfunction "B1_20") (pintype "bidirectional"))
    )
    (net (code "34") (name "GPIO6{slash}GPIO_PZ0") (class "Default")
      (node (ref "CON40") (pin "31") (pinfunction "GPIO6_31") (pintype "bidirectional"))
      (node (ref "R5") (pin "1") (pinfunction "1_1") (pintype "bidirectional"))
      (node (ref "U2") (pin "1") (pinfunction "A1_1") (pintype "bidirectional"))
    )
    (net (code "35") (name "GPIO10{slash}SPI1_MOSI") (class "Default")
      (node (ref "CON40") (pin "19") (pinfunction "MOSI_19") (pintype "bidirectional"))
      (node (ref "LED0") (pin "4-DIN") (pinfunction "DIN_4-DIN") (pintype "bidirectional"))
    )
    (net (code "36") (name "GPIO18{slash}I2S0_SCLK") (class "Default")
      (node (ref "CON40") (pin "12") (pinfunction "GPIO18_12") (pintype "bidirectional"))
      (node (ref "R10") (pin "1") (pinfunction "1_1") (pintype "bidirectional"))
      (node (ref "R12") (pin "1") (pinfunction "1_1") (pintype "bidirectional"))
      (node (ref "R19") (pin "1") (pinfunction "1_1") (pintype "bidirectional"))
    )
    (net (code "37") (name "GPIO19{slash}I2S0_FS") (class "Default")
      (node (ref "CON40") (pin "35") (pinfunction "GPIO19_35") (pintype "bidirectional"))
      (node (ref "R11") (pin "1") (pinfunction "1_1") (pintype "bidirectional"))
      (node (ref "R15") (pin "1") (pinfunction "1_1") (pintype "bidirectional"))
      (node (ref "R9") (pin "1") (pinfunction "1_1") (pintype "bidirectional"))
    )
    (net (code "38") (name "GPIO20{slash}I2S0_DIN") (class "Default")
      (node (ref "CON40") (pin "38") (pinfunction "GPIO20_38") (pintype "bidirectional"))
      (node (ref "R13") (pin "1") (pinfunction "1_1") (pintype "bidirectional"))
      (node (ref "R20") (pin "1") (pinfunction "1_1") (pintype "bidirectional"))
    )
    (net (code "39") (name "GPIO21{slash}I2S0_DOUT") (class "Default")
      (node (ref "CON40") (pin "40") (pinfunction "GPIO21_40") (pintype "bidirectional"))
      (node (ref "R16") (pin "1") (pinfunction "1_1") (pintype "bidirectional"))
    )
    (net (code "40") (name "JETSON3V3") (class "Default")
      (node (ref "C16") (pin "2") (pinfunction "2_2") (pintype "passive"))
      (node (ref "C17") (pin "2") (pinfunction "2_2") (pintype "passive"))
      (node (ref "C7") (pin "1") (pinfunction "1_1") (pintype "passive"))
      (node (ref "CON40") (pin "1") (pinfunction "3V3_1") (pintype "bidirectional"))
      (node (ref "CON40") (pin "17") (pinfunction "3V3_17") (pintype "bidirectional"))
      (node (ref "MIC_LEFT1") (pin "3") (pinfunction "VDD_3") (pintype "bidirectional"))
      (node (ref "MIC_RIGHT1") (pin "1") (pinfunction "LR_1") (pintype "bidirectional"))
      (node (ref "MIC_RIGHT1") (pin "3") (pinfunction "VDD_3") (pintype "bidirectional"))
      (node (ref "R22") (pin "2") (pinfunction "2_2") (pintype "bidirectional"))
      (node (ref "R23") (pin "2") (pinfunction "2_2") (pintype "bidirectional"))
      (node (ref "R3") (pin "1") (pinfunction "1_1") (pintype "bidirectional"))
      (node (ref "R4") (pin "2") (pinfunction "2_2") (pintype "bidirectional"))
      (node (ref "SJ3") (pin "1") (pinfunction "1_1") (pintype "passive"))
      (node (ref "U2") (pin "2") (pinfunction "VCCA_2") (pintype "bidirectional"))
    )
    (net (code "41") (name "JETSON　5V") (class "Default")
      (node (ref "C1") (pin "2") (pinfunction "2_2") (pintype "passive"))
      (node (ref "C10") (pin "1") (pinfunction "1_1") (pintype "passive"))
      (node (ref "C100") (pin "P$1") (pinfunction "1_P$1") (pintype "bidirectional"))
      (node (ref "C2") (pin "2") (pinfunction "2_2") (pintype "passive"))
      (node (ref "C3") (pin "2") (pinfunction "2_2") (pintype "passive"))
      (node (ref "C4") (pin "2") (pinfunction "2_2") (pintype "passive"))
      (node (ref "C5") (pin "2") (pinfunction "2_2") (pintype "passive"))
      (node (ref "CN3") (pin "1") (pinfunction "1_1") (pintype "bidirectional"))
      (node (ref "CON40") (pin "2") (pinfunction "5V_2") (pintype "bidirectional"))
      (node (ref "GPIO5,6,22") (pin "3") (pinfunction "3:VCC_3") (pintype "power_in"))
      (node (ref "I2C") (pin "3") (pinfunction "3:VCC_3") (pintype "power_in"))
      (node (ref "I2S0(DAP4)1") (pin "3") (pinfunction "3:VCC_3") (pintype "power_in"))
      (node (ref "LED0") (pin "1-VDD") (pinfunction "VDD_1-VDD") (pintype "bidirectional"))
      (node (ref "LED1") (pin "1-VDD") (pinfunction "VDD_1-VDD") (pintype "bidirectional"))
      (node (ref "LED2") (pin "1-VDD") (pinfunction "VDD_1-VDD") (pintype "bidirectional"))
      (node (ref "LED3") (pin "1-VDD") (pinfunction "VDD_1-VDD") (pintype "bidirectional"))
      (node (ref "LED4") (pin "1-VDD") (pinfunction "VDD_1-VDD") (pintype "bidirectional"))
      (node (ref "R21") (pin "2") (pinfunction "2_2") (pintype "bidirectional"))
      (node (ref "SJ3") (pin "2") (pinfunction "2_2") (pintype "passive"))
      (node (ref "SJ3") (pin "3") (pinfunction "3_3") (pintype "passive"))
      (node (ref "U$10") (pin "2:VCC3") (pinfunction "2:VCC_2:VCC3") (pintype "bidirectional"))
      (node (ref "U$16") (pin "2:VCC3") (pinfunction "2:VCC_2:VCC3") (pintype "bidirectional"))
      (node (ref "U1") (pin "3") (pinfunction "IN_3") (pintype "bidirectional"))
      (node (ref "U2") (pin "19") (pinfunction "VCCB_19") (pintype "bidirectional"))
    )
    (net (code "42") (name "Net-(C9-Pad2)") (class "Default")
      (node (ref "C9") (pin "2") (pinfunction "2_2") (pintype "passive"))
      (node (ref "L2") (pin "2") (pinfunction "2_2") (pintype "bidirectional"))
      (node (ref "L4") (pin "1") (pinfunction "1_1") (pintype "bidirectional"))
    )
    (net (code "43") (name "Net-(C21-Pad2)") (class "Default")
      (node (ref "C21") (pin "2") (pinfunction "2_2") (pintype "passive"))
      (node (ref "L1") (pin "2") (pinfunction "2_2") (pintype "bidirectional"))
      (node (ref "L3") (pin "1") (pinfunction "1_1") (pintype "bidirectional"))
    )
    (net (code "44") (name "Net-(CN4-Pad1)") (class "Default")
      (node (ref "CN4") (pin "1") (pinfunction "1_1") (pintype "bidirectional"))
      (node (ref "L3") (pin "2") (pinfunction "2_2") (pintype "bidirectional"))
      (node (ref "T3") (pin "P$1") (pinfunction "PIN1_P$1") (pintype "bidirectional"))
      (node (ref "T3") (pin "P$2") (pinfunction "PIN1_P$2") (pintype "bidirectional"))
      (node (ref "U$11") (pin "1") (pinfunction "1_1") (pintype "bidirectional"))
    )
    (net (code "45") (name "Net-(CN5-Pad1)") (class "Default")
      (node (ref "CN5") (pin "1") (pinfunction "1_1") (pintype "bidirectional"))
      (node (ref "L4") (pin "2") (pinfunction "2_2") (pintype "bidirectional"))
      (node (ref "T4") (pin "P$1") (pinfunction "PIN1_P$1") (pintype "bidirectional"))
      (node (ref "T4") (pin "P$2") (pinfunction "PIN1_P$2") (pintype "bidirectional"))
      (node (ref "U$12") (pin "1") (pinfunction "1_1") (pintype "bidirectional"))
    )
    (net (code "46") (name "Net-(GPIO5,6,22-5:PIN-A)") (class "Default")
      (node (ref "GPIO5,6,22") (pin "5") (pinfunction "5:PIN-A_5") (pintype "bidirectional"))
      (node (ref "R1") (pin "2") (pinfunction "2_2") (pintype "bidirectional"))
    )
    (net (code "47") (name "Net-(I2S0(DAP4)1-2:I2S_FS)") (class "Default")
      (node (ref "I2S0(DAP4)1") (pin "2") (pinfunction "2:I2S_FS_2") (pintype "input"))
      (node (ref "R15") (pin "2") (pinfunction "2_2") (pintype "bidirectional"))
    )
    (net (code "48") (name "Net-(I2S0(DAP4)1-4:I2S_SCLK)") (class "Default")
      (node (ref "I2S0(DAP4)1") (pin "4") (pinfunction "4:I2S_SCLK_4") (pintype "open_collector"))
      (node (ref "R19") (pin "2") (pinfunction "2_2") (pintype "bidirectional"))
    )
    (net (code "49") (name "Net-(I2S0(DAP4)1-5:I2S_DIN)") (class "Default")
      (node (ref "I2S0(DAP4)1") (pin "5") (pinfunction "5:I2S_DIN_5") (pintype "input"))
      (node (ref "R20") (pin "2") (pinfunction "2_2") (pintype "bidirectional"))
    )
    (net (code "50") (name "Net-(IC2-LED0)") (class "Default")
      (node (ref "IC2") (pin "3:LED0") (pinfunction "LED0_3:LED0") (pintype "bidirectional"))
      (node (ref "R7") (pin "2") (pinfunction "1_2") (pintype "bidirectional"))
    )
    (net (code "51") (name "Net-(IC2-LED1)") (class "Default")
      (node (ref "IC2") (pin "4:LED1") (pinfunction "LED1_4:LED1") (pintype "bidirectional"))
      (node (ref "R7") (pin "1") (pinfunction "1_1") (pintype "bidirectional"))
    )
    (net (code "52") (name "Net-(LED0-DOUT)") (class "Default")
      (node (ref "LED0") (pin "2-DOUT") (pinfunction "DOUT_2-DOUT") (pintype "bidirectional"))
      (node (ref "LED1") (pin "4-DIN") (pinfunction "DIN_4-DIN") (pintype "bidirectional"))
    )
    (net (code "53") (name "Net-(LED1-DOUT)") (class "Default")
      (node (ref "LED1") (pin "2-DOUT") (pinfunction "DOUT_2-DOUT") (pintype "bidirectional"))
      (node (ref "LED2") (pin "4-DIN") (pinfunction "DIN_4-DIN") (pintype "bidirectional"))
    )
    (net (code "54") (name "Net-(LED2-DOUT)") (class "Default")
      (node (ref "LED2") (pin "2-DOUT") (pinfunction "DOUT_2-DOUT") (pintype "bidirectional"))
      (node (ref "LED3") (pin "4-DIN") (pinfunction "DIN_4-DIN") (pintype "bidirectional"))
    )
    (net (code "55") (name "Net-(LED3-DOUT)") (class "Default")
      (node (ref "LED3") (pin "2-DOUT") (pinfunction "DOUT_2-DOUT") (pintype "bidirectional"))
      (node (ref "LED4") (pin "4-DIN") (pinfunction "DIN_4-DIN") (pintype "bidirectional"))
    )
    (net (code "56") (name "Net-(LED5-PadANODE)") (class "Default")
      (node (ref "LED5") (pin "ANODE") (pinfunction "ANODE_ANODE") (pintype "passive"))
      (node (ref "R21") (pin "1") (pinfunction "1_1") (pintype "bidirectional"))
    )
    (net (code "57") (name "Net-(R7A-2)") (class "Default")
      (node (ref "R7") (pin "8") (pinfunction "2_8") (pintype "bidirectional"))
      (node (ref "U$16") (pin "1:SIGNAL3") (pinfunction "1:SIGNAL_1:SIGNAL3") (pintype "output"))
    )
    (net (code "58") (name "Net-(R7B-2)") (class "Default")
      (node (ref "R7") (pin "7") (pinfunction "2_7") (pintype "bidirectional"))
      (node (ref "U$10") (pin "1:SIGNAL3") (pinfunction "1:SIGNAL_1:SIGNAL3") (pintype "output"))
    )
    (net (code "59") (name "Net-(R17-Pad2)") (class "Default")
      (node (ref "R17") (pin "2") (pinfunction "2_2") (pintype "bidirectional"))
      (node (ref "U$14") (pin "2") (pinfunction "2_2") (pintype "bidirectional"))
    )
    (net (code "60") (name "Net-(R18-Pad1)") (class "Default")
      (node (ref "R18") (pin "1") (pinfunction "1_1") (pintype "bidirectional"))
      (node (ref "U$14") (pin "4") (pinfunction "4_4") (pintype "bidirectional"))
    )
    (net (code "61") (name "Net-(U$13-2:GAIN)") (class "Default")
      (node (ref "U$13") (pin "2") (pinfunction "2:GAIN_2") (pintype "bidirectional"))
      (node (ref "U$14") (pin "1") (pinfunction "1_1") (pintype "bidirectional"))
    )
    (net (code "62") (name "Net-(U$13-4:SD_MODE)") (class "Default")
      (node (ref "R6") (pin "2") (pinfunction "2_2") (pintype "bidirectional"))
      (node (ref "U$13") (pin "4") (pinfunction "4:SD_MODE_4") (pintype "bidirectional"))
    )
    (net (code "63") (name "Net-(U$13-9:OUTP)") (class "Default")
      (node (ref "L1") (pin "1") (pinfunction "1_1") (pintype "bidirectional"))
      (node (ref "U$13") (pin "9") (pinfunction "9:OUTP_9") (pintype "bidirectional"))
    )
    (net (code "64") (name "Net-(U$13-10:OUTN)") (class "Default")
      (node (ref "L2") (pin "1") (pinfunction "1_1") (pintype "bidirectional"))
      (node (ref "U$13") (pin "10") (pinfunction "10:OUTN_10") (pintype "bidirectional"))
    )
    (net (code "65") (name "Net-(U2-OE)") (class "Default")
      (node (ref "R24") (pin "2") (pinfunction "2_2") (pintype "bidirectional"))
      (node (ref "R4") (pin "1") (pinfunction "1_1") (pintype "bidirectional"))
      (node (ref "U2") (pin "10") (pinfunction "OE_10") (pintype "bidirectional"))
    )
    (net (code "66") (name "unconnected-(GPIO5,6,22-2:NC-Pad2)") (class "Default")
      (node (ref "GPIO5,6,22") (pin "2") (pinfunction "2:NC_2") (pintype "no_connect"))
    )
    (net (code "67") (name "unconnected-(GPIO5,6,22-4:PIN-C-Pad4)") (class "Default")
      (node (ref "GPIO5,6,22") (pin "4") (pinfunction "4:PIN-C_4") (pintype "bidirectional"))
    )
    (net (code "68") (name "unconnected-(GPIO5,6,22-6:PIN-B-Pad6)") (class "Default")
      (node (ref "GPIO5,6,22") (pin "6") (pinfunction "6:PIN-B_6") (pintype "bidirectional"))
    )
    (net (code "69") (name "unconnected-(I2C-2:NC-Pad2)") (class "Default")
      (node (ref "I2C") (pin "2") (pinfunction "2:NC_2") (pintype "no_connect"))
    )
    (net (code "70") (name "unconnected-(I2C-6:NC-Pad6)") (class "Default")
      (node (ref "I2C") (pin "6") (pinfunction "6:NC_6") (pintype "no_connect"))
    )
    (net (code "71") (name "unconnected-(I2S0(DAP4)1-6:I2S_OUT-Pad6)") (class "Default")
      (node (ref "I2S0(DAP4)1") (pin "6") (pinfunction "6:I2S_OUT_6") (pintype "output"))
    )
    (net (code "72") (name "unconnected-(IC2-LED2-Pad5:LED2)") (class "Default")
      (node (ref "IC2") (pin "5:LED2") (pinfunction "LED2_5:LED2") (pintype "bidirectional"))
    )
    (net (code "73") (name "unconnected-(IC2-LED3-Pad6:LED3)") (class "Default")
      (node (ref "IC2") (pin "6:LED3") (pinfunction "LED3_6:LED3") (pintype "bidirectional"))
    )
    (net (code "74") (name "unconnected-(IC2-LED4-Pad7:LED4)") (class "Default")
      (node (ref "IC2") (pin "7:LED4") (pinfunction "LED4_7:LED4") (pintype "bidirectional"))
    )
    (net (code "75") (name "unconnected-(IC2-LED5-Pad8:LED5)") (class "Default")
      (node (ref "IC2") (pin "8:LED5") (pinfunction "LED5_8:LED5") (pintype "bidirectional"))
    )
    (net (code "76") (name "unconnected-(IC2-LED6-Pad9:LED6)") (class "Default")
      (node (ref "IC2") (pin "9:LED6") (pinfunction "LED6_9:LED6") (pintype "bidirectional"))
    )
    (net (code "77") (name "unconnected-(IC2-LED7-Pad10:LED7)") (class "Default")
      (node (ref "IC2") (pin "10:LED7") (pinfunction "LED7_10:LED7") (pintype "bidirectional"))
    )
    (net (code "78") (name "unconnected-(IC2-LED8-Pad12:LED8)") (class "Default")
      (node (ref "IC2") (pin "12:LED8") (pinfunction "LED8_12:LED8") (pintype "bidirectional"))
    )
    (net (code "79") (name "unconnected-(IC2-LED9-Pad13:LED9)") (class "Default")
      (node (ref "IC2") (pin "13:LED9") (pinfunction "LED9_13:LED9") (pintype "bidirectional"))
    )
    (net (code "80") (name "unconnected-(IC2-LED10-Pad14:LED10)") (class "Default")
      (node (ref "IC2") (pin "14:LED10") (pinfunction "LED10_14:LED10") (pintype "bidirectional"))
    )
    (net (code "81") (name "unconnected-(IC2-LED11-Pad15:LED11)") (class "Default")
      (node (ref "IC2") (pin "15:LED11") (pinfunction "LED11_15:LED11") (pintype "bidirectional"))
    )
    (net (code "82") (name "unconnected-(IC2-LED12-Pad16:LED12)") (class "Default")
      (node (ref "IC2") (pin "16:LED12") (pinfunction "LED12_16:LED12") (pintype "bidirectional"))
    )
    (net (code "83") (name "unconnected-(IC2-LED13-Pad17:LED13)") (class "Default")
      (node (ref "IC2") (pin "17:LED13") (pinfunction "LED13_17:LED13") (pintype "bidirectional"))
    )
    (net (code "84") (name "unconnected-(IC2-LED14-Pad18:LED14)") (class "Default")
      (node (ref "IC2") (pin "18:LED14") (pinfunction "LED14_18:LED14") (pintype "bidirectional"))
    )
    (net (code "85") (name "unconnected-(IC2-LED15-Pad19:LED15)") (class "Default")
      (node (ref "IC2") (pin "19:LED15") (pinfunction "LED15_19:LED15") (pintype "bidirectional"))
    )
    (net (code "86") (name "unconnected-(LED4-DOUT-Pad2-DOUT)") (class "Default")
      (node (ref "LED4") (pin "2-DOUT") (pinfunction "DOUT_2-DOUT") (pintype "bidirectional"))
    )
    (net (code "87") (name "unconnected-(R7C-1-Pad3)") (class "Default")
      (node (ref "R7") (pin "3") (pinfunction "1_3") (pintype "bidirectional"))
    )
    (net (code "88") (name "unconnected-(R7C-2-Pad6)") (class "Default")
      (node (ref "R7") (pin "6") (pinfunction "2_6") (pintype "bidirectional"))
    )
    (net (code "89") (name "unconnected-(R7D-1-Pad4)") (class "Default")
      (node (ref "R7") (pin "4") (pinfunction "1_4") (pintype "bidirectional"))
    )
    (net (code "90") (name "unconnected-(R7D-2-Pad5)") (class "Default")
      (node (ref "R7") (pin "5") (pinfunction "2_5") (pintype "bidirectional"))
    )
    (net (code "91") (name "unconnected-(U$13-5:NC-Pad5)") (class "Default")
      (node (ref "U$13") (pin "5") (pinfunction "5:NC_5") (pintype "no_connect"))
    )
    (net (code "92") (name "unconnected-(U$13-6:NC-Pad6)") (class "Default")
      (node (ref "U$13") (pin "6") (pinfunction "6:NC_6") (pintype "no_connect"))
    )
    (net (code "93") (name "unconnected-(U$13-12:NC-Pad12)") (class "Default")
      (node (ref "U$13") (pin "12") (pinfunction "12:NC_12") (pintype "no_connect"))
    )
    (net (code "94") (name "unconnected-(U$13-13:NC-Pad13)") (class "Default")
      (node (ref "U$13") (pin "13") (pinfunction "13:NC_13") (pintype "no_connect"))
    )
    (net (code "95") (name "unconnected-(U2-A2-Pad3)") (class "Default")
      (node (ref "U2") (pin "3") (pinfunction "A2_3") (pintype "bidirectional"))
    )
    (net (code "96") (name "unconnected-(U2-A3-Pad4)") (class "Default")
      (node (ref "U2") (pin "4") (pinfunction "A3_4") (pintype "bidirectional"))
    )
    (net (code "97") (name "unconnected-(U2-A4-Pad5)") (class "Default")
      (node (ref "U2") (pin "5") (pinfunction "A4_5") (pintype "bidirectional"))
    )
    (net (code "98") (name "unconnected-(U2-A5-Pad6)") (class "Default")
      (node (ref "U2") (pin "6") (pinfunction "A5_6") (pintype "bidirectional"))
    )
    (net (code "99") (name "unconnected-(U2-A6-Pad7)") (class "Default")
      (node (ref "U2") (pin "7") (pinfunction "A6_7") (pintype "bidirectional"))
    )
    (net (code "100") (name "unconnected-(U2-A7-Pad8)") (class "Default")
      (node (ref "U2") (pin "8") (pinfunction "A7_8") (pintype "bidirectional"))
    )
    (net (code "101") (name "unconnected-(U2-A8-Pad9)") (class "Default")
      (node (ref "U2") (pin "9") (pinfunction "A8_9") (pintype "bidirectional"))
    )
    (net (code "102") (name "unconnected-(U2-B2-Pad18)") (class "Default")
      (node (ref "U2") (pin "18") (pinfunction "B2_18") (pintype "bidirectional"))
    )
    (net (code "103") (name "unconnected-(U2-B3-Pad17)") (class "Default")
      (node (ref "U2") (pin "17") (pinfunction "B3_17") (pintype "bidirectional"))
    )
    (net (code "104") (name "unconnected-(U2-B4-Pad16)") (class "Default")
      (node (ref "U2") (pin "16") (pinfunction "B4_16") (pintype "bidirectional"))
    )
    (net (code "105") (name "unconnected-(U2-B5-Pad15)") (class "Default")
      (node (ref "U2") (pin "15") (pinfunction "B5_15") (pintype "bidirectional"))
    )
    (net (code "106") (name "unconnected-(U2-B6-Pad14)") (class "Default")
      (node (ref "U2") (pin "14") (pinfunction "B6_14") (pintype "bidirectional"))
    )
    (net (code "107") (name "unconnected-(U2-B7-Pad13)") (class "Default")
      (node (ref "U2") (pin "13") (pinfunction "B7_13") (pintype "bidirectional"))
    )
    (net (code "108") (name "unconnected-(U2-B8-Pad12)") (class "Default")
      (node (ref "U2") (pin "12") (pinfunction "B8_12") (pintype "bidirectional"))
    )
  )
)
